# WAK-Shield-v11.net
KiCad netlist of a schematic drawn in EAGLE
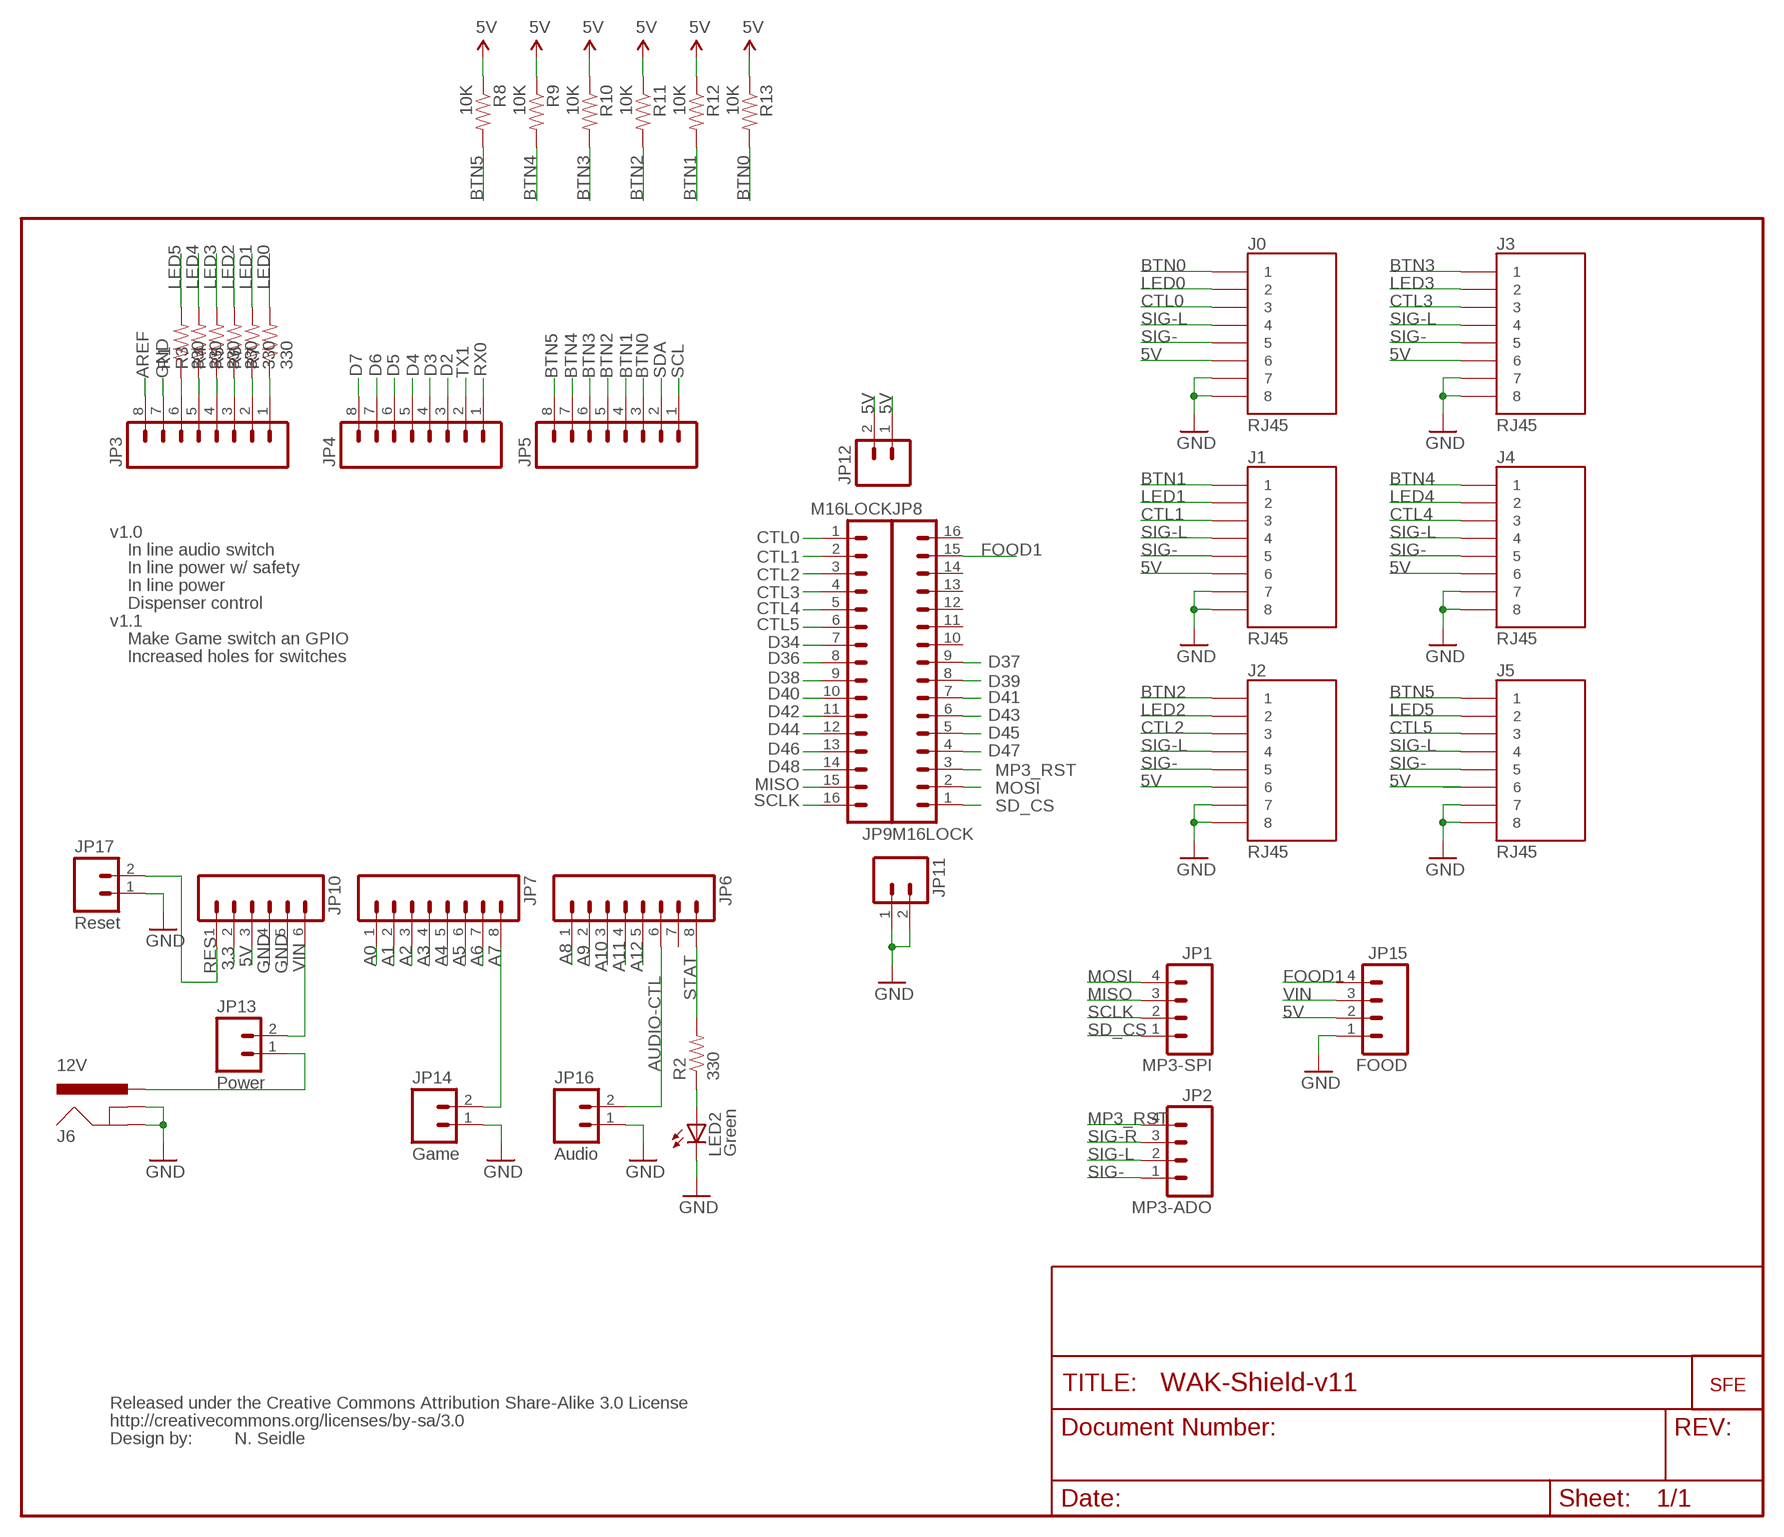
[diagram p0: schematic, sheet 1]

(export (version "E")
  (design (tool "Eeschema 10.0.6"))
  (components
    (comp (ref "J0")
      (value "RJ45")
      (footprint "eagle-import:RJ45-8")
      (libsource (lib "eagle-import") (part "RJ45-8PTH"))
    )
    (comp (ref "J1")
      (value "RJ45")
      (footprint "eagle-import:RJ45-8")
      (libsource (lib "eagle-import") (part "RJ45-8PTH"))
    )
    (comp (ref "J2")
      (value "RJ45")
      (footprint "eagle-import:RJ45-8")
      (libsource (lib "eagle-import") (part "RJ45-8PTH"))
    )
    (comp (ref "J3")
      (value "RJ45")
      (footprint "eagle-import:RJ45-8")
      (libsource (lib "eagle-import") (part "RJ45-8PTH"))
    )
    (comp (ref "J4")
      (value "RJ45")
      (footprint "eagle-import:RJ45-8")
      (libsource (lib "eagle-import") (part "RJ45-8PTH"))
    )
    (comp (ref "J5")
      (value "RJ45")
      (footprint "eagle-import:RJ45-8")
      (libsource (lib "eagle-import") (part "RJ45-8PTH"))
    )
    (comp (ref "J6")
      (value "12V")
      (footprint "eagle-import:POWER_JACK_PTH_LOCK")
      (libsource (lib "eagle-import") (part "POWER_JACKPTH_LOCK"))
    )
    (comp (ref "JP1")
      (value "MP3-SPI")
      (footprint "eagle-import:JST-4-PTH")
      (libsource (lib "eagle-import") (part "M04JST-PTH"))
    )
    (comp (ref "JP2")
      (value "MP3-ADO")
      (footprint "eagle-import:JST-4-PTH")
      (libsource (lib "eagle-import") (part "M04JST-PTH"))
    )
    (comp (ref "JP3")
      (value "M08LOCK")
      (footprint "eagle-import:1X08_LOCK")
      (libsource (lib "eagle-import") (part "M08LOCK"))
    )
    (comp (ref "JP4")
      (value "M08LOCK")
      (footprint "eagle-import:1X08_LOCK")
      (libsource (lib "eagle-import") (part "M08LOCK"))
    )
    (comp (ref "JP5")
      (value "M08LOCK")
      (footprint "eagle-import:1X08_LOCK")
      (libsource (lib "eagle-import") (part "M08LOCK"))
    )
    (comp (ref "JP6")
      (value "M08LOCK")
      (footprint "eagle-import:1X08_LOCK")
      (libsource (lib "eagle-import") (part "M08LOCK"))
    )
    (comp (ref "JP7")
      (value "M08LOCK")
      (footprint "eagle-import:1X08_LOCK")
      (libsource (lib "eagle-import") (part "M08LOCK"))
    )
    (comp (ref "JP8")
      (value "M16LOCK")
      (footprint "eagle-import:1X16_LOCK")
      (libsource (lib "eagle-import") (part "M16LOCK"))
    )
    (comp (ref "JP9")
      (value "M16LOCK")
      (footprint "eagle-import:1X16_LOCK")
      (libsource (lib "eagle-import") (part "M16LOCK"))
    )
    (comp (ref "JP10")
      (value "M06LOCK")
      (footprint "eagle-import:1X06_LOCK")
      (libsource (lib "eagle-import") (part "M06LOCK"))
    )
    (comp (ref "JP11")
      (value "M02LOCK")
      (footprint "eagle-import:1X02_LOCK")
      (libsource (lib "eagle-import") (part "M02LOCK"))
    )
    (comp (ref "JP12")
      (value "M02LOCK")
      (footprint "eagle-import:1X02_LOCK")
      (libsource (lib "eagle-import") (part "M02LOCK"))
    )
    (comp (ref "JP13")
      (value "Power")
      (footprint "eagle-import:1X02")
      (libsource (lib "eagle-import") (part "SparkFun-Connectors_M02PTH"))
    )
    (comp (ref "JP14")
      (value "Game")
      (footprint "eagle-import:1X02")
      (libsource (lib "eagle-import") (part "SparkFun-Connectors_M02PTH"))
    )
    (comp (ref "JP15")
      (value "FOOD")
      (footprint "eagle-import:JST-4-PTH")
      (libsource (lib "eagle-import") (part "M04JST-PTH"))
    )
    (comp (ref "JP16")
      (value "Audio")
      (footprint "eagle-import:1X02")
      (libsource (lib "eagle-import") (part "SparkFun-Connectors_M02PTH"))
    )
    (comp (ref "JP17")
      (value "Reset")
      (footprint "eagle-import:SCREWTERMINAL-3.5MM-2")
      (libsource (lib "eagle-import") (part "SparkFun-Connectors_M023.5MM"))
    )
    (comp (ref "LED2")
      (value "Green")
      (footprint "eagle-import:LED5MM")
      (libsource (lib "eagle-import") (part "LED5MM"))
    )
    (comp (ref "R1")
      (value "330")
      (footprint "eagle-import:AXIAL-0.3")
      (libsource (lib "eagle-import") (part "RESISTORPTH1"))
    )
    (comp (ref "R2")
      (value "330")
      (footprint "eagle-import:AXIAL-0.3")
      (libsource (lib "eagle-import") (part "RESISTORPTH1"))
    )
    (comp (ref "R3")
      (value "330")
      (footprint "eagle-import:AXIAL-0.3")
      (libsource (lib "eagle-import") (part "RESISTORPTH1"))
    )
    (comp (ref "R4")
      (value "330")
      (footprint "eagle-import:AXIAL-0.3")
      (libsource (lib "eagle-import") (part "RESISTORPTH1"))
    )
    (comp (ref "R5")
      (value "330")
      (footprint "eagle-import:AXIAL-0.3")
      (libsource (lib "eagle-import") (part "RESISTORPTH1"))
    )
    (comp (ref "R6")
      (value "330")
      (footprint "eagle-import:AXIAL-0.3")
      (libsource (lib "eagle-import") (part "RESISTORPTH1"))
    )
    (comp (ref "R7")
      (value "330")
      (footprint "eagle-import:AXIAL-0.3")
      (libsource (lib "eagle-import") (part "RESISTORPTH1"))
    )
    (comp (ref "R8")
      (value "10K")
      (footprint "eagle-import:AXIAL-0.3")
      (libsource (lib "eagle-import") (part "RESISTORPTH1"))
    )
    (comp (ref "R9")
      (value "10K")
      (footprint "eagle-import:AXIAL-0.3")
      (libsource (lib "eagle-import") (part "RESISTORPTH1"))
    )
    (comp (ref "R10")
      (value "10K")
      (footprint "eagle-import:AXIAL-0.3")
      (libsource (lib "eagle-import") (part "RESISTORPTH1"))
    )
    (comp (ref "R11")
      (value "10K")
      (footprint "eagle-import:AXIAL-0.3")
      (libsource (lib "eagle-import") (part "RESISTORPTH1"))
    )
    (comp (ref "R12")
      (value "10K")
      (footprint "eagle-import:AXIAL-0.3")
      (libsource (lib "eagle-import") (part "RESISTORPTH1"))
    )
    (comp (ref "R13")
      (value "10K")
      (footprint "eagle-import:AXIAL-0.3")
      (libsource (lib "eagle-import") (part "RESISTORPTH1"))
    )
    (comp (ref "U$1")
      (value "LOGO-SFENEW")
      (footprint "eagle-import:SFE-NEW-WEBLOGO")
      (libsource (lib "eagle-import") (part "LOGO-SFENEW"))
    )
    (comp (ref "U$2")
      (value "CREATIVE_COMMONS")
      (footprint "eagle-import:CREATIVE_COMMONS")
      (libsource (lib "eagle-import") (part "CREATIVE_COMMONS"))
    )
  )
  (nets
    (net (code "1") (name "/3.3") (class "Default")
      (node (ref "JP10") (pin "2") (pinfunction "2_2") (pintype "passive"))
    )
    (net (code "2") (name "/A0") (class "Default")
      (node (ref "JP7") (pin "1") (pinfunction "1_1") (pintype "passive"))
    )
    (net (code "3") (name "/A1") (class "Default")
      (node (ref "JP7") (pin "2") (pinfunction "2_2") (pintype "passive"))
    )
    (net (code "4") (name "/A2") (class "Default")
      (node (ref "JP7") (pin "3") (pinfunction "3_3") (pintype "passive"))
    )
    (net (code "5") (name "/A3") (class "Default")
      (node (ref "JP7") (pin "4") (pinfunction "4_4") (pintype "passive"))
    )
    (net (code "6") (name "/A4") (class "Default")
      (node (ref "JP7") (pin "5") (pinfunction "5_5") (pintype "passive"))
    )
    (net (code "7") (name "/A5") (class "Default")
      (node (ref "JP7") (pin "6") (pinfunction "6_6") (pintype "passive"))
    )
    (net (code "8") (name "/A6") (class "Default")
      (node (ref "JP7") (pin "7") (pinfunction "7_7") (pintype "passive"))
    )
    (net (code "9") (name "/A7") (class "Default")
      (node (ref "JP14") (pin "2") (pinfunction "2_2") (pintype "passive"))
      (node (ref "JP7") (pin "8") (pinfunction "8_8") (pintype "passive"))
    )
    (net (code "10") (name "/A8") (class "Default")
      (node (ref "JP6") (pin "1") (pinfunction "1_1") (pintype "passive"))
    )
    (net (code "11") (name "/A9") (class "Default")
      (node (ref "JP6") (pin "2") (pinfunction "2_2") (pintype "passive"))
    )
    (net (code "12") (name "/A10") (class "Default")
      (node (ref "JP6") (pin "3") (pinfunction "3_3") (pintype "passive"))
    )
    (net (code "13") (name "/A11") (class "Default")
      (node (ref "JP6") (pin "4") (pinfunction "4_4") (pintype "passive"))
    )
    (net (code "14") (name "/A12") (class "Default")
      (node (ref "JP6") (pin "5") (pinfunction "5_5") (pintype "passive"))
    )
    (net (code "15") (name "/AREF") (class "Default")
      (node (ref "JP3") (pin "8") (pinfunction "8_8") (pintype "passive"))
    )
    (net (code "16") (name "/AUDIO-CTL") (class "Default")
      (node (ref "JP16") (pin "2") (pinfunction "2_2") (pintype "passive"))
      (node (ref "JP6") (pin "6") (pinfunction "6_6") (pintype "passive"))
    )
    (net (code "17") (name "/BTN0") (class "Default")
      (node (ref "J0") (pin "1") (pinfunction "1_1") (pintype "bidirectional"))
      (node (ref "JP5") (pin "3") (pinfunction "3_3") (pintype "passive"))
      (node (ref "R13") (pin "P$2") (pinfunction "2_P$2") (pintype "passive"))
    )
    (net (code "18") (name "/BTN1") (class "Default")
      (node (ref "J1") (pin "1") (pinfunction "1_1") (pintype "bidirectional"))
      (node (ref "JP5") (pin "4") (pinfunction "4_4") (pintype "passive"))
      (node (ref "R12") (pin "P$2") (pinfunction "2_P$2") (pintype "passive"))
    )
    (net (code "19") (name "/BTN2") (class "Default")
      (node (ref "J2") (pin "1") (pinfunction "1_1") (pintype "bidirectional"))
      (node (ref "JP5") (pin "5") (pinfunction "5_5") (pintype "passive"))
      (node (ref "R11") (pin "P$2") (pinfunction "2_P$2") (pintype "passive"))
    )
    (net (code "20") (name "/BTN3") (class "Default")
      (node (ref "J3") (pin "1") (pinfunction "1_1") (pintype "bidirectional"))
      (node (ref "JP5") (pin "6") (pinfunction "6_6") (pintype "passive"))
      (node (ref "R10") (pin "P$2") (pinfunction "2_P$2") (pintype "passive"))
    )
    (net (code "21") (name "/BTN4") (class "Default")
      (node (ref "J4") (pin "1") (pinfunction "1_1") (pintype "bidirectional"))
      (node (ref "JP5") (pin "7") (pinfunction "7_7") (pintype "passive"))
      (node (ref "R9") (pin "P$2") (pinfunction "2_P$2") (pintype "passive"))
    )
    (net (code "22") (name "/BTN5") (class "Default")
      (node (ref "J5") (pin "1") (pinfunction "1_1") (pintype "bidirectional"))
      (node (ref "JP5") (pin "8") (pinfunction "8_8") (pintype "passive"))
      (node (ref "R8") (pin "P$2") (pinfunction "2_P$2") (pintype "passive"))
    )
    (net (code "23") (name "/CTL0") (class "Default")
      (node (ref "J0") (pin "3") (pinfunction "3_3") (pintype "bidirectional"))
      (node (ref "JP9") (pin "1") (pinfunction "1_1") (pintype "passive"))
    )
    (net (code "24") (name "/CTL1") (class "Default")
      (node (ref "J1") (pin "3") (pinfunction "3_3") (pintype "bidirectional"))
      (node (ref "JP9") (pin "2") (pinfunction "2_2") (pintype "passive"))
    )
    (net (code "25") (name "/CTL2") (class "Default")
      (node (ref "J2") (pin "3") (pinfunction "3_3") (pintype "bidirectional"))
      (node (ref "JP9") (pin "3") (pinfunction "3_3") (pintype "passive"))
    )
    (net (code "26") (name "/CTL3") (class "Default")
      (node (ref "J3") (pin "3") (pinfunction "3_3") (pintype "bidirectional"))
      (node (ref "JP9") (pin "4") (pinfunction "4_4") (pintype "passive"))
    )
    (net (code "27") (name "/CTL4") (class "Default")
      (node (ref "J4") (pin "3") (pinfunction "3_3") (pintype "bidirectional"))
      (node (ref "JP9") (pin "5") (pinfunction "5_5") (pintype "passive"))
    )
    (net (code "28") (name "/CTL5") (class "Default")
      (node (ref "J5") (pin "3") (pinfunction "3_3") (pintype "bidirectional"))
      (node (ref "JP9") (pin "6") (pinfunction "6_6") (pintype "passive"))
    )
    (net (code "29") (name "/D2") (class "Default")
      (node (ref "JP4") (pin "3") (pinfunction "3_3") (pintype "passive"))
    )
    (net (code "30") (name "/D3") (class "Default")
      (node (ref "JP4") (pin "4") (pinfunction "4_4") (pintype "passive"))
    )
    (net (code "31") (name "/D4") (class "Default")
      (node (ref "JP4") (pin "5") (pinfunction "5_5") (pintype "passive"))
    )
    (net (code "32") (name "/D5") (class "Default")
      (node (ref "JP4") (pin "6") (pinfunction "6_6") (pintype "passive"))
    )
    (net (code "33") (name "/D6") (class "Default")
      (node (ref "JP4") (pin "7") (pinfunction "7_7") (pintype "passive"))
    )
    (net (code "34") (name "/D7") (class "Default")
      (node (ref "JP4") (pin "8") (pinfunction "8_8") (pintype "passive"))
    )
    (net (code "35") (name "/D34") (class "Default")
      (node (ref "JP9") (pin "7") (pinfunction "7_7") (pintype "passive"))
    )
    (net (code "36") (name "/D36") (class "Default")
      (node (ref "JP9") (pin "8") (pinfunction "8_8") (pintype "passive"))
    )
    (net (code "37") (name "/D37") (class "Default")
      (node (ref "JP8") (pin "9") (pinfunction "9_9") (pintype "passive"))
    )
    (net (code "38") (name "/D38") (class "Default")
      (node (ref "JP9") (pin "9") (pinfunction "9_9") (pintype "passive"))
    )
    (net (code "39") (name "/D39") (class "Default")
      (node (ref "JP8") (pin "8") (pinfunction "8_8") (pintype "passive"))
    )
    (net (code "40") (name "/D40") (class "Default")
      (node (ref "JP9") (pin "10") (pinfunction "10_10") (pintype "passive"))
    )
    (net (code "41") (name "/D41") (class "Default")
      (node (ref "JP8") (pin "7") (pinfunction "7_7") (pintype "passive"))
    )
    (net (code "42") (name "/D42") (class "Default")
      (node (ref "JP9") (pin "11") (pinfunction "11_11") (pintype "passive"))
    )
    (net (code "43") (name "/D43") (class "Default")
      (node (ref "JP8") (pin "6") (pinfunction "6_6") (pintype "passive"))
    )
    (net (code "44") (name "/D44") (class "Default")
      (node (ref "JP9") (pin "12") (pinfunction "12_12") (pintype "passive"))
    )
    (net (code "45") (name "/D45") (class "Default")
      (node (ref "JP8") (pin "5") (pinfunction "5_5") (pintype "passive"))
    )
    (net (code "46") (name "/D46") (class "Default")
      (node (ref "JP9") (pin "13") (pinfunction "13_13") (pintype "passive"))
    )
    (net (code "47") (name "/D47") (class "Default")
      (node (ref "JP8") (pin "4") (pinfunction "4_4") (pintype "passive"))
    )
    (net (code "48") (name "/D48") (class "Default")
      (node (ref "JP9") (pin "14") (pinfunction "14_14") (pintype "passive"))
    )
    (net (code "49") (name "/FOOD1") (class "Default")
      (node (ref "JP15") (pin "4") (pinfunction "4_4") (pintype "passive"))
      (node (ref "JP8") (pin "15") (pinfunction "15_15") (pintype "passive"))
    )
    (net (code "50") (name "/LED0") (class "Default")
      (node (ref "J0") (pin "2") (pinfunction "2_2") (pintype "bidirectional"))
      (node (ref "R7") (pin "P$2") (pinfunction "2_P$2") (pintype "passive"))
    )
    (net (code "51") (name "/LED1") (class "Default")
      (node (ref "J1") (pin "2") (pinfunction "2_2") (pintype "bidirectional"))
      (node (ref "R6") (pin "P$2") (pinfunction "2_P$2") (pintype "passive"))
    )
    (net (code "52") (name "/LED2") (class "Default")
      (node (ref "J2") (pin "2") (pinfunction "2_2") (pintype "bidirectional"))
      (node (ref "R5") (pin "P$2") (pinfunction "2_P$2") (pintype "passive"))
    )
    (net (code "53") (name "/LED3") (class "Default")
      (node (ref "J3") (pin "2") (pinfunction "2_2") (pintype "bidirectional"))
      (node (ref "R4") (pin "P$2") (pinfunction "2_P$2") (pintype "passive"))
    )
    (net (code "54") (name "/LED4") (class "Default")
      (node (ref "J4") (pin "2") (pinfunction "2_2") (pintype "bidirectional"))
      (node (ref "R3") (pin "P$2") (pinfunction "2_P$2") (pintype "passive"))
    )
    (net (code "55") (name "/LED5") (class "Default")
      (node (ref "J5") (pin "2") (pinfunction "2_2") (pintype "bidirectional"))
      (node (ref "R1") (pin "P$2") (pinfunction "2_P$2") (pintype "passive"))
    )
    (net (code "56") (name "/MISO") (class "Default")
      (node (ref "JP1") (pin "3") (pinfunction "3_3") (pintype "passive"))
      (node (ref "JP9") (pin "15") (pinfunction "15_15") (pintype "passive"))
    )
    (net (code "57") (name "/MOSI") (class "Default")
      (node (ref "JP1") (pin "4") (pinfunction "4_4") (pintype "passive"))
      (node (ref "JP8") (pin "2") (pinfunction "2_2") (pintype "passive"))
    )
    (net (code "58") (name "/MP3_RST") (class "Default")
      (node (ref "JP2") (pin "4") (pinfunction "4_4") (pintype "passive"))
      (node (ref "JP8") (pin "3") (pinfunction "3_3") (pintype "passive"))
    )
    (net (code "59") (name "/RES") (class "Default")
      (node (ref "JP10") (pin "1") (pinfunction "1_1") (pintype "passive"))
      (node (ref "JP17") (pin "2") (pinfunction "2_2") (pintype "passive"))
    )
    (net (code "60") (name "/RX0") (class "Default")
      (node (ref "JP4") (pin "1") (pinfunction "1_1") (pintype "passive"))
    )
    (net (code "61") (name "/SCL") (class "Default")
      (node (ref "JP5") (pin "1") (pinfunction "1_1") (pintype "passive"))
    )
    (net (code "62") (name "/SCLK") (class "Default")
      (node (ref "JP1") (pin "2") (pinfunction "2_2") (pintype "passive"))
      (node (ref "JP9") (pin "16") (pinfunction "16_16") (pintype "passive"))
    )
    (net (code "63") (name "/SDA") (class "Default")
      (node (ref "JP5") (pin "2") (pinfunction "2_2") (pintype "passive"))
    )
    (net (code "64") (name "/SD_CS") (class "Default")
      (node (ref "JP1") (pin "1") (pinfunction "1_1") (pintype "passive"))
      (node (ref "JP8") (pin "1") (pinfunction "1_1") (pintype "passive"))
    )
    (net (code "65") (name "/SIG-") (class "Default")
      (node (ref "J0") (pin "5") (pinfunction "5_5") (pintype "bidirectional"))
      (node (ref "J1") (pin "5") (pinfunction "5_5") (pintype "bidirectional"))
      (node (ref "J2") (pin "5") (pinfunction "5_5") (pintype "bidirectional"))
      (node (ref "J3") (pin "5") (pinfunction "5_5") (pintype "bidirectional"))
      (node (ref "J4") (pin "5") (pinfunction "5_5") (pintype "bidirectional"))
      (node (ref "J5") (pin "5") (pinfunction "5_5") (pintype "bidirectional"))
      (node (ref "JP2") (pin "1") (pinfunction "1_1") (pintype "passive"))
    )
    (net (code "66") (name "/SIG-L") (class "Default")
      (node (ref "J0") (pin "4") (pinfunction "4_4") (pintype "bidirectional"))
      (node (ref "J1") (pin "4") (pinfunction "4_4") (pintype "bidirectional"))
      (node (ref "J2") (pin "4") (pinfunction "4_4") (pintype "bidirectional"))
      (node (ref "J3") (pin "4") (pinfunction "4_4") (pintype "bidirectional"))
      (node (ref "J4") (pin "4") (pinfunction "4_4") (pintype "bidirectional"))
      (node (ref "J5") (pin "4") (pinfunction "4_4") (pintype "bidirectional"))
      (node (ref "JP2") (pin "2") (pinfunction "2_2") (pintype "passive"))
    )
    (net (code "67") (name "/SIG-R") (class "Default")
      (node (ref "JP2") (pin "3") (pinfunction "3_3") (pintype "passive"))
    )
    (net (code "68") (name "/STAT") (class "Default")
      (node (ref "JP6") (pin "8") (pinfunction "8_8") (pintype "passive"))
      (node (ref "R2") (pin "P$2") (pinfunction "2_P$2") (pintype "passive"))
    )
    (net (code "69") (name "/TX1") (class "Default")
      (node (ref "JP4") (pin "2") (pinfunction "2_2") (pintype "passive"))
    )
    (net (code "70") (name "/VIN") (class "Default")
      (node (ref "JP10") (pin "6") (pinfunction "6_6") (pintype "passive"))
      (node (ref "JP13") (pin "2") (pinfunction "2_2") (pintype "passive"))
      (node (ref "JP15") (pin "3") (pinfunction "3_3") (pintype "passive"))
    )
    (net (code "71") (name "5V") (class "Default")
      (node (ref "J0") (pin "6") (pinfunction "6_6") (pintype "bidirectional"))
      (node (ref "J1") (pin "6") (pinfunction "6_6") (pintype "bidirectional"))
      (node (ref "J2") (pin "6") (pinfunction "6_6") (pintype "bidirectional"))
      (node (ref "J3") (pin "6") (pinfunction "6_6") (pintype "bidirectional"))
      (node (ref "J4") (pin "6") (pinfunction "6_6") (pintype "bidirectional"))
      (node (ref "J5") (pin "6") (pinfunction "6_6") (pintype "bidirectional"))
      (node (ref "JP10") (pin "3") (pinfunction "3_3") (pintype "passive"))
      (node (ref "JP12") (pin "1") (pinfunction "1_1") (pintype "passive"))
      (node (ref "JP12") (pin "2") (pinfunction "2_2") (pintype "passive"))
      (node (ref "JP15") (pin "2") (pinfunction "2_2") (pintype "passive"))
      (node (ref "R10") (pin "P$1") (pinfunction "1_P$1") (pintype "passive"))
      (node (ref "R11") (pin "P$1") (pinfunction "1_P$1") (pintype "passive"))
      (node (ref "R12") (pin "P$1") (pinfunction "1_P$1") (pintype "passive"))
      (node (ref "R13") (pin "P$1") (pinfunction "1_P$1") (pintype "passive"))
      (node (ref "R8") (pin "P$1") (pinfunction "1_P$1") (pintype "passive"))
      (node (ref "R9") (pin "P$1") (pinfunction "1_P$1") (pintype "passive"))
    )
    (net (code "72") (name "GND") (class "Default")
      (node (ref "J0") (pin "7") (pinfunction "7_7") (pintype "bidirectional"))
      (node (ref "J0") (pin "8") (pinfunction "8_8") (pintype "bidirectional"))
      (node (ref "J1") (pin "7") (pinfunction "7_7") (pintype "bidirectional"))
      (node (ref "J1") (pin "8") (pinfunction "8_8") (pintype "bidirectional"))
      (node (ref "J2") (pin "7") (pinfunction "7_7") (pintype "bidirectional"))
      (node (ref "J2") (pin "8") (pinfunction "8_8") (pintype "bidirectional"))
      (node (ref "J3") (pin "7") (pinfunction "7_7") (pintype "bidirectional"))
      (node (ref "J3") (pin "8") (pinfunction "8_8") (pintype "bidirectional"))
      (node (ref "J4") (pin "7") (pinfunction "7_7") (pintype "bidirectional"))
      (node (ref "J4") (pin "8") (pinfunction "8_8") (pintype "bidirectional"))
      (node (ref "J5") (pin "7") (pinfunction "7_7") (pintype "bidirectional"))
      (node (ref "J5") (pin "8") (pinfunction "8_8") (pintype "bidirectional"))
      (node (ref "J6") (pin "GND") (pinfunction "GND_GND") (pintype "bidirectional"))
      (node (ref "J6") (pin "GNDBREAK") (pinfunction "GNDBREAK_GNDBREAK") (pintype "bidirectional"))
      (node (ref "JP10") (pin "4") (pinfunction "4_4") (pintype "passive"))
      (node (ref "JP10") (pin "5") (pinfunction "5_5") (pintype "passive"))
      (node (ref "JP11") (pin "1") (pinfunction "1_1") (pintype "passive"))
      (node (ref "JP11") (pin "2") (pinfunction "2_2") (pintype "passive"))
      (node (ref "JP14") (pin "1") (pinfunction "1_1") (pintype "passive"))
      (node (ref "JP15") (pin "1") (pinfunction "1_1") (pintype "passive"))
      (node (ref "JP16") (pin "1") (pinfunction "1_1") (pintype "passive"))
      (node (ref "JP17") (pin "1") (pinfunction "1_1") (pintype "passive"))
      (node (ref "JP3") (pin "7") (pinfunction "7_7") (pintype "passive"))
      (node (ref "LED2") (pin "K") (pinfunction "C_K") (pintype "passive"))
    )
    (net (code "73") (name "Net-(J6-PadPWR)") (class "Default")
      (node (ref "J6") (pin "PWR") (pinfunction "PWR_PWR") (pintype "bidirectional"))
      (node (ref "JP13") (pin "1") (pinfunction "1_1") (pintype "passive"))
    )
    (net (code "74") (name "Net-(R1-1)") (class "Default")
      (node (ref "JP3") (pin "6") (pinfunction "6_6") (pintype "passive"))
      (node (ref "R1") (pin "P$1") (pinfunction "1_P$1") (pintype "passive"))
    )
    (net (code "75") (name "Net-(R2-1)") (class "Default")
      (node (ref "LED2") (pin "A") (pinfunction "A_A") (pintype "passive"))
      (node (ref "R2") (pin "P$1") (pinfunction "1_P$1") (pintype "passive"))
    )
    (net (code "76") (name "Net-(R3-1)") (class "Default")
      (node (ref "JP3") (pin "5") (pinfunction "5_5") (pintype "passive"))
      (node (ref "R3") (pin "P$1") (pinfunction "1_P$1") (pintype "passive"))
    )
    (net (code "77") (name "Net-(R4-1)") (class "Default")
      (node (ref "JP3") (pin "4") (pinfunction "4_4") (pintype "passive"))
      (node (ref "R4") (pin "P$1") (pinfunction "1_P$1") (pintype "passive"))
    )
    (net (code "78") (name "Net-(R5-1)") (class "Default")
      (node (ref "JP3") (pin "3") (pinfunction "3_3") (pintype "passive"))
      (node (ref "R5") (pin "P$1") (pinfunction "1_P$1") (pintype "passive"))
    )
    (net (code "79") (name "Net-(R6-1)") (class "Default")
      (node (ref "JP3") (pin "2") (pinfunction "2_2") (pintype "passive"))
      (node (ref "R6") (pin "P$1") (pinfunction "1_P$1") (pintype "passive"))
    )
    (net (code "80") (name "Net-(R7-1)") (class "Default")
      (node (ref "JP3") (pin "1") (pinfunction "1_1") (pintype "passive"))
      (node (ref "R7") (pin "P$1") (pinfunction "1_P$1") (pintype "passive"))
    )
    (net (code "81") (name "unconnected-(JP6-Pad7)") (class "Default")
      (node (ref "JP6") (pin "7") (pinfunction "7_7") (pintype "passive"))
    )
    (net (code "82") (name "unconnected-(JP8-Pad10)") (class "Default")
      (node (ref "JP8") (pin "10") (pinfunction "10_10") (pintype "passive"))
    )
    (net (code "83") (name "unconnected-(JP8-Pad11)") (class "Default")
      (node (ref "JP8") (pin "11") (pinfunction "11_11") (pintype "passive"))
    )
    (net (code "84") (name "unconnected-(JP8-Pad12)") (class "Default")
      (node (ref "JP8") (pin "12") (pinfunction "12_12") (pintype "passive"))
    )
    (net (code "85") (name "unconnected-(JP8-Pad13)") (class "Default")
      (node (ref "JP8") (pin "13") (pinfunction "13_13") (pintype "passive"))
    )
    (net (code "86") (name "unconnected-(JP8-Pad14)") (class "Default")
      (node (ref "JP8") (pin "14") (pinfunction "14_14") (pintype "passive"))
    )
    (net (code "87") (name "unconnected-(JP8-Pad16)") (class "Default")
      (node (ref "JP8") (pin "16") (pinfunction "16_16") (pintype "passive"))
    )
  )
)
